# SensorPod.net
KiCad netlist of a schematic drawn in EAGLE
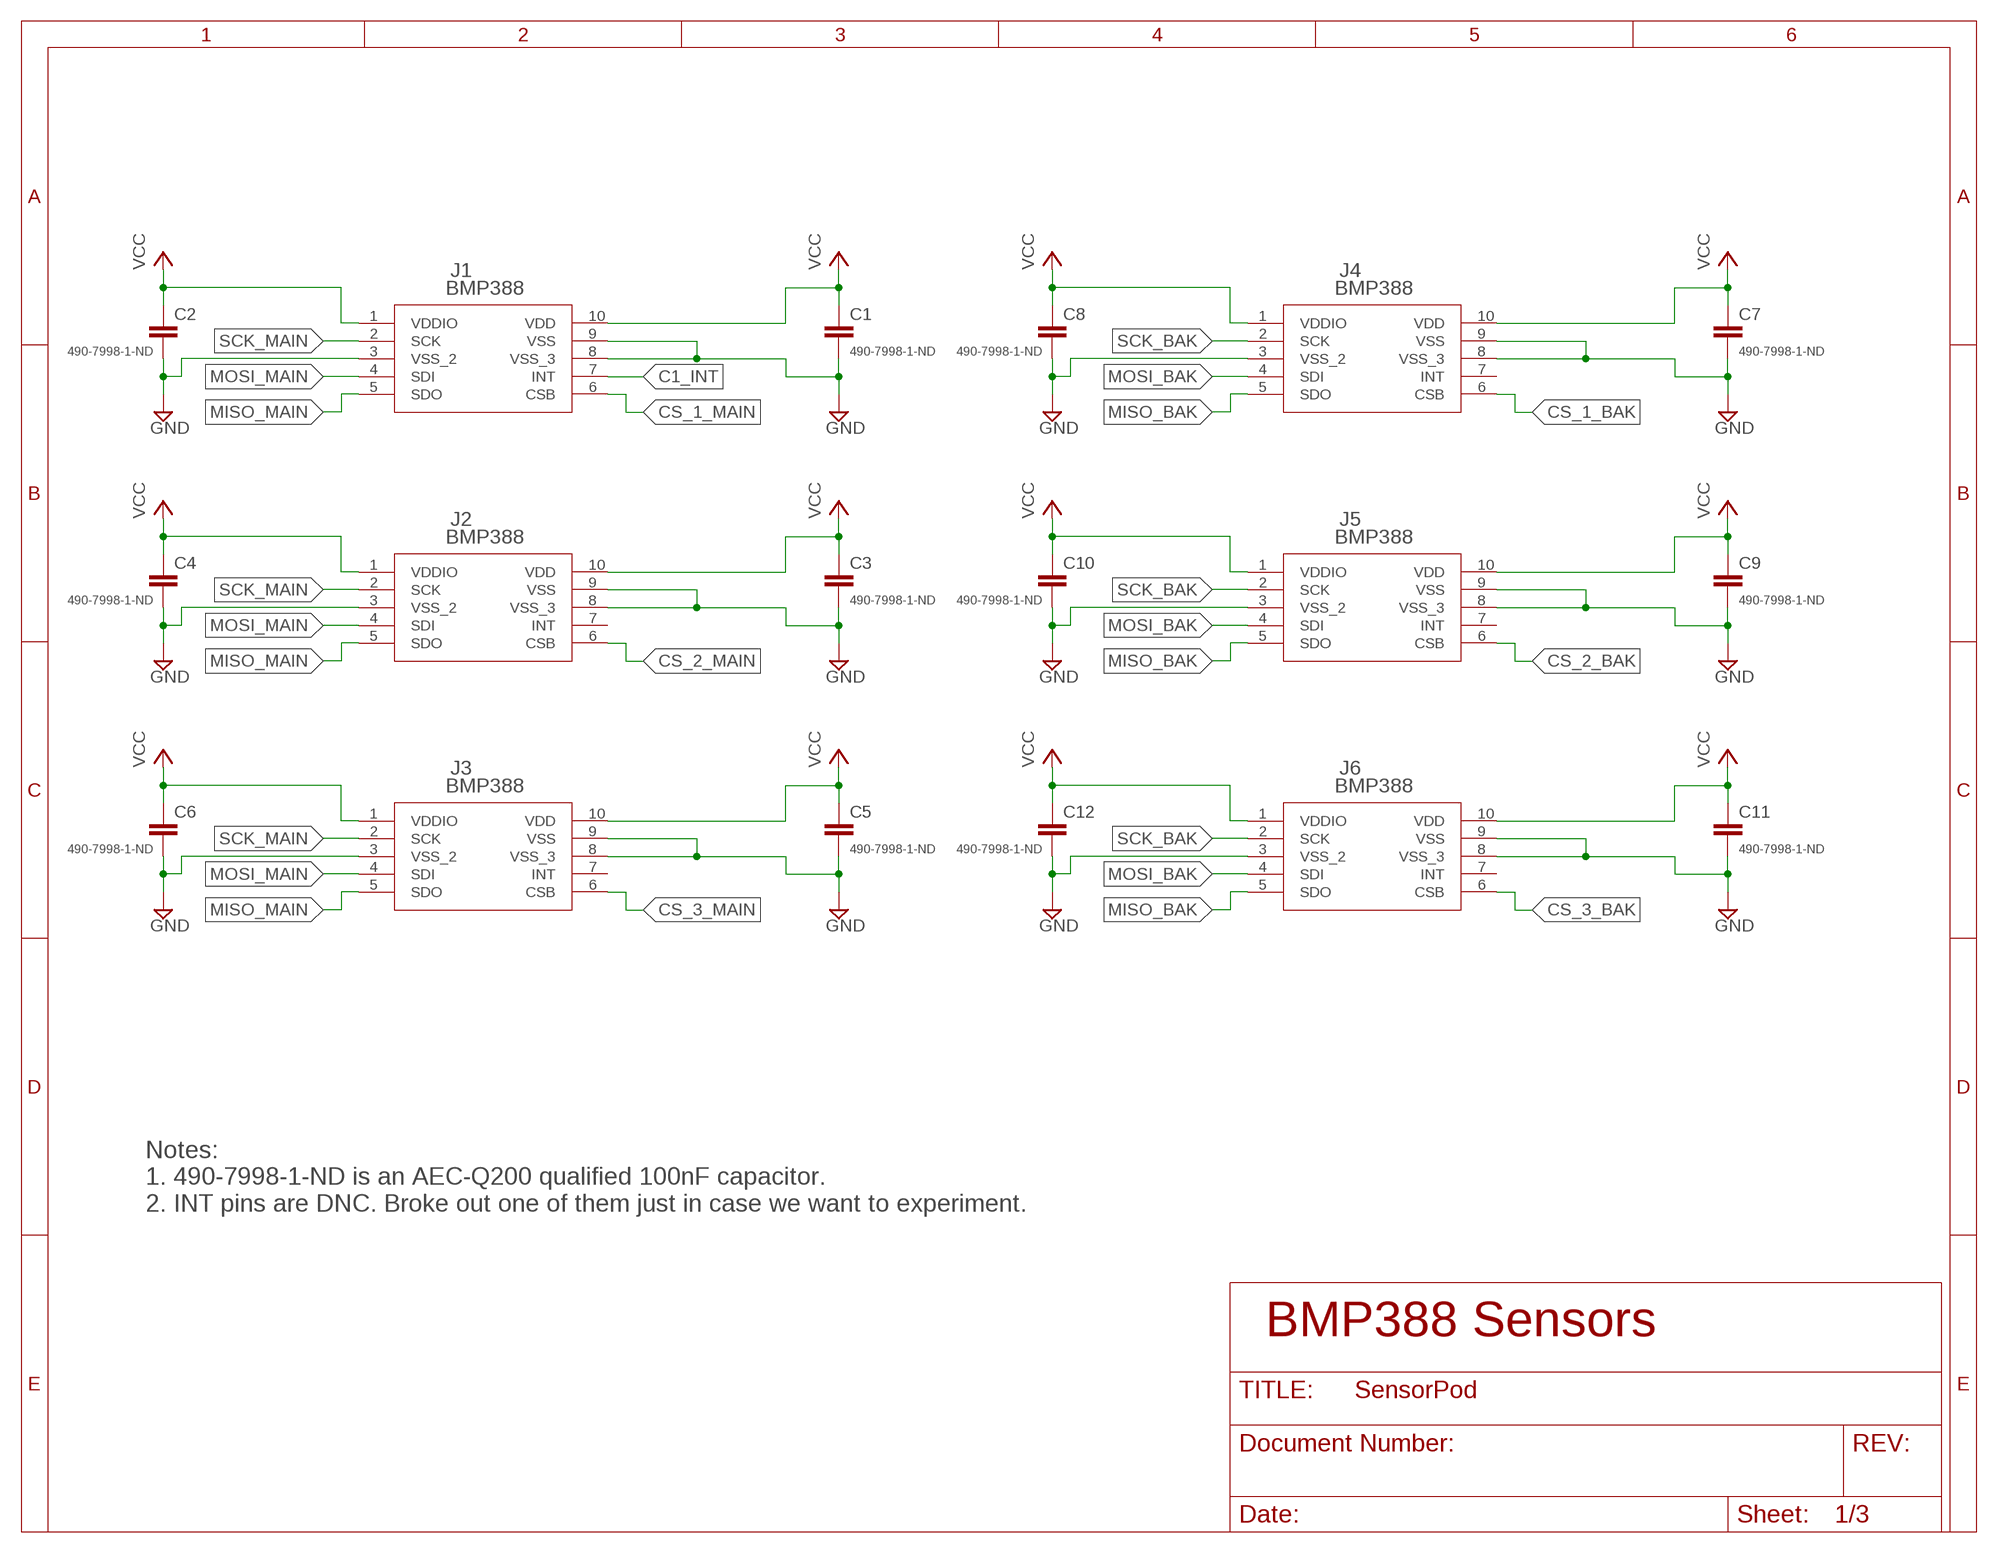
[diagram p0: schematic, sheet 1]
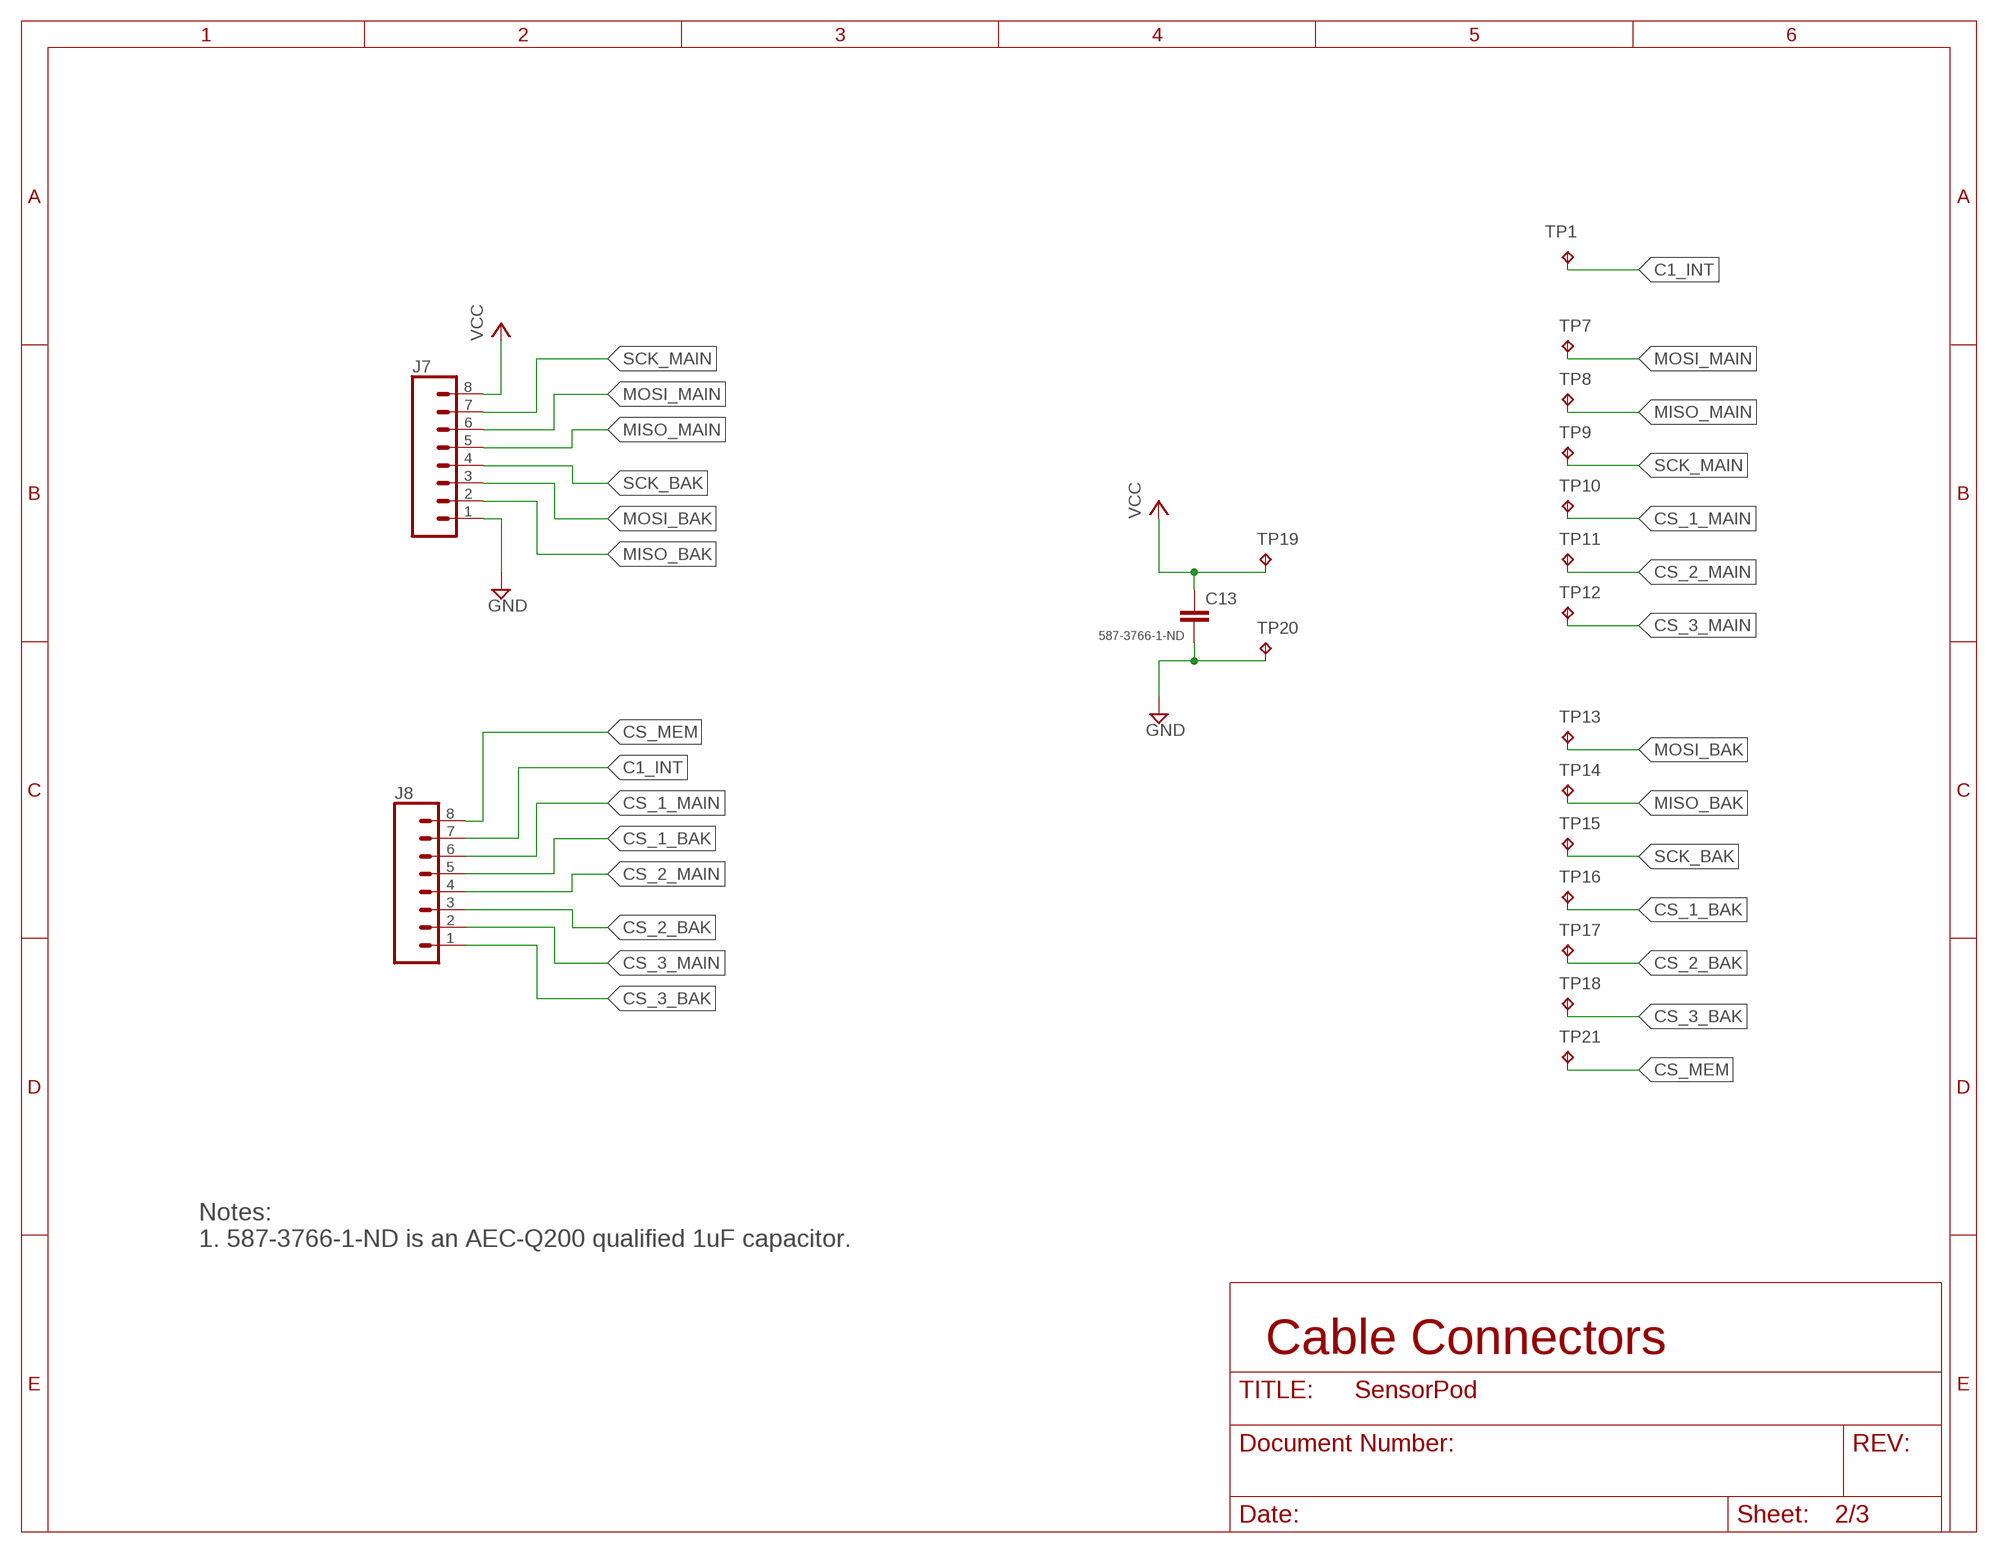
[diagram p1: schematic, sheet 2]
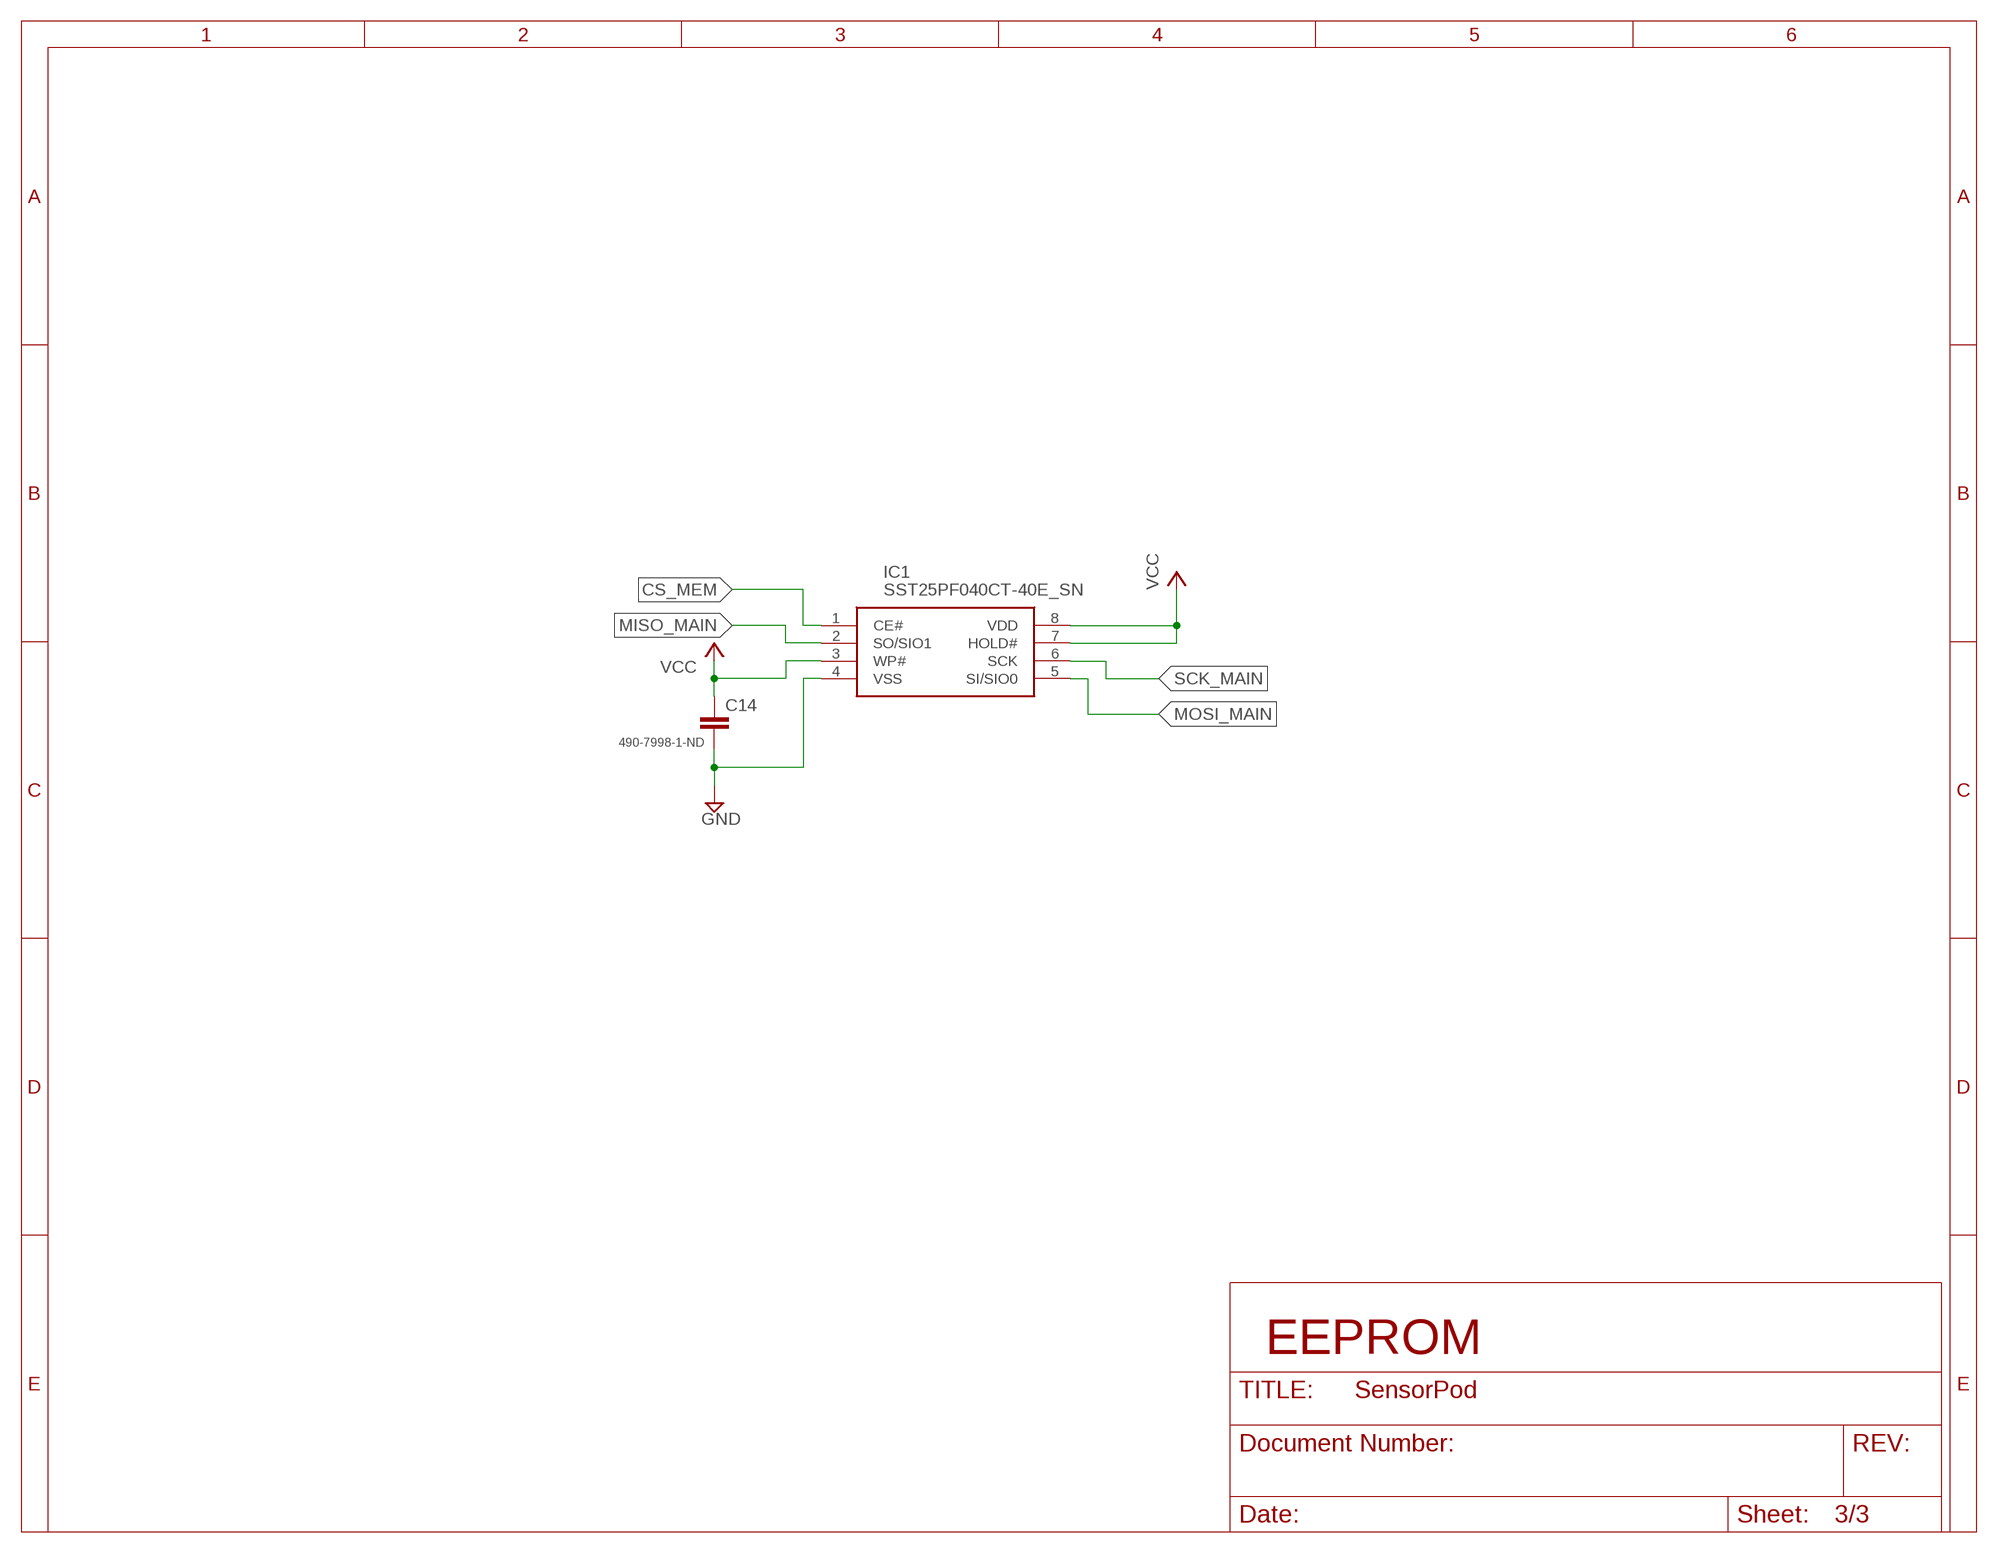
[diagram p2: schematic, sheet 3]

(export (version "E")
  (design (tool "Eeschema 10.0.6"))
  (components
    (comp (ref "C1")
      (value "490-7998-1-ND")
      (footprint "eagle-import:C0402")
      (libsource (lib "eagle-import") (part "C-EUC0402"))
    )
    (comp (ref "C2")
      (value "490-7998-1-ND")
      (footprint "eagle-import:C0402")
      (libsource (lib "eagle-import") (part "C-EUC0402"))
    )
    (comp (ref "C3")
      (value "490-7998-1-ND")
      (footprint "eagle-import:C0402")
      (libsource (lib "eagle-import") (part "C-EUC0402"))
    )
    (comp (ref "C4")
      (value "490-7998-1-ND")
      (footprint "eagle-import:C0402")
      (libsource (lib "eagle-import") (part "C-EUC0402"))
    )
    (comp (ref "C5")
      (value "490-7998-1-ND")
      (footprint "eagle-import:C0402")
      (libsource (lib "eagle-import") (part "C-EUC0402"))
    )
    (comp (ref "C6")
      (value "490-7998-1-ND")
      (footprint "eagle-import:C0402")
      (libsource (lib "eagle-import") (part "C-EUC0402"))
    )
    (comp (ref "C7")
      (value "490-7998-1-ND")
      (footprint "eagle-import:C0402")
      (libsource (lib "eagle-import") (part "C-EUC0402"))
    )
    (comp (ref "C8")
      (value "490-7998-1-ND")
      (footprint "eagle-import:C0402")
      (libsource (lib "eagle-import") (part "C-EUC0402"))
    )
    (comp (ref "C9")
      (value "490-7998-1-ND")
      (footprint "eagle-import:C0402")
      (libsource (lib "eagle-import") (part "C-EUC0402"))
    )
    (comp (ref "C10")
      (value "490-7998-1-ND")
      (footprint "eagle-import:C0402")
      (libsource (lib "eagle-import") (part "C-EUC0402"))
    )
    (comp (ref "C11")
      (value "490-7998-1-ND")
      (footprint "eagle-import:C0402")
      (libsource (lib "eagle-import") (part "C-EUC0402"))
    )
    (comp (ref "C12")
      (value "490-7998-1-ND")
      (footprint "eagle-import:C0402")
      (libsource (lib "eagle-import") (part "C-EUC0402"))
    )
    (comp (ref "J1")
      (value "BMP388")
      (footprint "eagle-import:QFN_BMP388")
      (fields (field (name "COPYRIGHT") "Copyright (C) 2018 Accelerated Designs. All rights reserved"))
      (libsource (lib "eagle-import") (part "BMP388"))
    )
    (comp (ref "J2")
      (value "BMP388")
      (footprint "eagle-import:QFN_BMP388")
      (fields (field (name "COPYRIGHT") "Copyright (C) 2018 Accelerated Designs. All rights reserved"))
      (libsource (lib "eagle-import") (part "BMP388"))
    )
    (comp (ref "J3")
      (value "BMP388")
      (footprint "eagle-import:QFN_BMP388")
      (fields (field (name "COPYRIGHT") "Copyright (C) 2018 Accelerated Designs. All rights reserved"))
      (libsource (lib "eagle-import") (part "BMP388"))
    )
    (comp (ref "J4")
      (value "BMP388")
      (footprint "eagle-import:QFN_BMP388")
      (fields (field (name "COPYRIGHT") "Copyright (C) 2018 Accelerated Designs. All rights reserved"))
      (libsource (lib "eagle-import") (part "BMP388"))
    )
    (comp (ref "J5")
      (value "BMP388")
      (footprint "eagle-import:QFN_BMP388")
      (fields (field (name "COPYRIGHT") "Copyright (C) 2018 Accelerated Designs. All rights reserved"))
      (libsource (lib "eagle-import") (part "BMP388"))
    )
    (comp (ref "J6")
      (value "BMP388")
      (footprint "eagle-import:QFN_BMP388")
      (fields (field (name "COPYRIGHT") "Copyright (C) 2018 Accelerated Designs. All rights reserved"))
      (libsource (lib "eagle-import") (part "BMP388"))
    )
    (comp (ref "C14")
      (value "490-7998-1-ND")
      (footprint "eagle-import:C0402")
      (libsource (lib "eagle-import") (part "C-EUC0402"))
    )
    (comp (ref "IC1")
      (value "SST25PF040CT-40E_SN")
      (footprint "eagle-import:SOIC127P600X175-8N")
      (fields
        (field (name "MANUFACTURER_PART_NUMBER") "SST25PF040CT-40E/SN")
        (field (name "MOUSER_PART_NUMBER") "579-T25PF040CT-40ESN")
      )
      (libsource (lib "eagle-import") (part "SST25PF040CT-40E_SN"))
    )
    (comp (ref "C13")
      (value "587-3766-1-ND")
      (footprint "eagle-import:C0402")
      (libsource (lib "eagle-import") (part "C-EUC0402"))
    )
    (comp (ref "J7")
      (value "CONN_08\"")
      (footprint "eagle-import:1X08")
      (libsource (lib "eagle-import") (part "CONN_08{dblquote}"))
    )
    (comp (ref "J8")
      (value "CONN_08\"")
      (footprint "eagle-import:1X08")
      (libsource (lib "eagle-import") (part "CONN_08{dblquote}"))
    )
    (comp (ref "TP1")
      (value "TPB1,27")
      (footprint "eagle-import:B1,27")
      (libsource (lib "eagle-import") (part "TPB1,27"))
    )
    (comp (ref "TP7")
      (value "TPB1,27")
      (footprint "eagle-import:B1,27")
      (libsource (lib "eagle-import") (part "TPB1,27"))
    )
    (comp (ref "TP8")
      (value "TPB1,27")
      (footprint "eagle-import:B1,27")
      (libsource (lib "eagle-import") (part "TPB1,27"))
    )
    (comp (ref "TP9")
      (value "TPB1,27")
      (footprint "eagle-import:B1,27")
      (libsource (lib "eagle-import") (part "TPB1,27"))
    )
    (comp (ref "TP10")
      (value "TPB1,27")
      (footprint "eagle-import:B1,27")
      (libsource (lib "eagle-import") (part "TPB1,27"))
    )
    (comp (ref "TP11")
      (value "TPB1,27")
      (footprint "eagle-import:B1,27")
      (libsource (lib "eagle-import") (part "TPB1,27"))
    )
    (comp (ref "TP12")
      (value "TPB1,27")
      (footprint "eagle-import:B1,27")
      (libsource (lib "eagle-import") (part "TPB1,27"))
    )
    (comp (ref "TP13")
      (value "TPB1,27")
      (footprint "eagle-import:B1,27")
      (libsource (lib "eagle-import") (part "TPB1,27"))
    )
    (comp (ref "TP14")
      (value "TPB1,27")
      (footprint "eagle-import:B1,27")
      (libsource (lib "eagle-import") (part "TPB1,27"))
    )
    (comp (ref "TP15")
      (value "TPB1,27")
      (footprint "eagle-import:B1,27")
      (libsource (lib "eagle-import") (part "TPB1,27"))
    )
    (comp (ref "TP16")
      (value "TPB1,27")
      (footprint "eagle-import:B1,27")
      (libsource (lib "eagle-import") (part "TPB1,27"))
    )
    (comp (ref "TP17")
      (value "TPB1,27")
      (footprint "eagle-import:B1,27")
      (libsource (lib "eagle-import") (part "TPB1,27"))
    )
    (comp (ref "TP18")
      (value "TPB1,27")
      (footprint "eagle-import:B1,27")
      (libsource (lib "eagle-import") (part "TPB1,27"))
    )
    (comp (ref "TP19")
      (value "TPB1,27")
      (footprint "eagle-import:B1,27")
      (libsource (lib "eagle-import") (part "TPB1,27"))
    )
    (comp (ref "TP20")
      (value "TPB1,27")
      (footprint "eagle-import:B1,27")
      (libsource (lib "eagle-import") (part "TPB1,27"))
    )
    (comp (ref "TP21")
      (value "TPB1,27")
      (footprint "eagle-import:B1,27")
      (libsource (lib "eagle-import") (part "TPB1,27"))
    )
  )
  (nets
    (net (code "1") (name "C1_INT") (class "Default")
      (node (ref "J1") (pin "7") (pinfunction "INT_7") (pintype "passive"))
      (node (ref "J8") (pin "7") (pinfunction "7_7") (pintype "passive"))
      (node (ref "TP1") (pin "TP") (pinfunction "TP_TP") (pintype "input"))
    )
    (net (code "2") (name "CS_1_BAK") (class "Default")
      (node (ref "J4") (pin "6") (pinfunction "CSB_6") (pintype "passive"))
      (node (ref "J8") (pin "5") (pinfunction "5_5") (pintype "passive"))
      (node (ref "TP16") (pin "TP") (pinfunction "TP_TP") (pintype "input"))
    )
    (net (code "3") (name "CS_1_MAIN") (class "Default")
      (node (ref "J1") (pin "6") (pinfunction "CSB_6") (pintype "passive"))
      (node (ref "J8") (pin "6") (pinfunction "6_6") (pintype "passive"))
      (node (ref "TP10") (pin "TP") (pinfunction "TP_TP") (pintype "input"))
    )
    (net (code "4") (name "CS_2_BAK") (class "Default")
      (node (ref "J5") (pin "6") (pinfunction "CSB_6") (pintype "passive"))
      (node (ref "J8") (pin "3") (pinfunction "3_3") (pintype "passive"))
      (node (ref "TP17") (pin "TP") (pinfunction "TP_TP") (pintype "input"))
    )
    (net (code "5") (name "CS_2_MAIN") (class "Default")
      (node (ref "J2") (pin "6") (pinfunction "CSB_6") (pintype "passive"))
      (node (ref "J8") (pin "4") (pinfunction "4_4") (pintype "passive"))
      (node (ref "TP11") (pin "TP") (pinfunction "TP_TP") (pintype "input"))
    )
    (net (code "6") (name "CS_3_BAK") (class "Default")
      (node (ref "J6") (pin "6") (pinfunction "CSB_6") (pintype "passive"))
      (node (ref "J8") (pin "1") (pinfunction "1_1") (pintype "passive"))
      (node (ref "TP18") (pin "TP") (pinfunction "TP_TP") (pintype "input"))
    )
    (net (code "7") (name "CS_3_MAIN") (class "Default")
      (node (ref "J3") (pin "6") (pinfunction "CSB_6") (pintype "passive"))
      (node (ref "J8") (pin "2") (pinfunction "2_2") (pintype "passive"))
      (node (ref "TP12") (pin "TP") (pinfunction "TP_TP") (pintype "input"))
    )
    (net (code "8") (name "CS_MEM") (class "Default")
      (node (ref "IC1") (pin "1") (pinfunction "CE#_1") (pintype "bidirectional"))
      (node (ref "J8") (pin "8") (pinfunction "8_8") (pintype "passive"))
      (node (ref "TP21") (pin "TP") (pinfunction "TP_TP") (pintype "input"))
    )
    (net (code "9") (name "GND") (class "Default")
      (node (ref "C1") (pin "2") (pinfunction "2_2") (pintype "passive"))
      (node (ref "C10") (pin "2") (pinfunction "2_2") (pintype "passive"))
      (node (ref "C11") (pin "2") (pinfunction "2_2") (pintype "passive"))
      (node (ref "C12") (pin "2") (pinfunction "2_2") (pintype "passive"))
      (node (ref "C13") (pin "2") (pinfunction "2_2") (pintype "passive"))
      (node (ref "C14") (pin "2") (pinfunction "2_2") (pintype "passive"))
      (node (ref "C2") (pin "2") (pinfunction "2_2") (pintype "passive"))
      (node (ref "C3") (pin "2") (pinfunction "2_2") (pintype "passive"))
      (node (ref "C4") (pin "2") (pinfunction "2_2") (pintype "passive"))
      (node (ref "C5") (pin "2") (pinfunction "2_2") (pintype "passive"))
      (node (ref "C6") (pin "2") (pinfunction "2_2") (pintype "passive"))
      (node (ref "C7") (pin "2") (pinfunction "2_2") (pintype "passive"))
      (node (ref "C8") (pin "2") (pinfunction "2_2") (pintype "passive"))
      (node (ref "C9") (pin "2") (pinfunction "2_2") (pintype "passive"))
      (node (ref "IC1") (pin "4") (pinfunction "VSS_4") (pintype "bidirectional"))
      (node (ref "J1") (pin "3") (pinfunction "VSS_2_3") (pintype "passive"))
      (node (ref "J1") (pin "8") (pinfunction "VSS_3_8") (pintype "passive"))
      (node (ref "J1") (pin "9") (pinfunction "VSS_9") (pintype "passive"))
      (node (ref "J2") (pin "3") (pinfunction "VSS_2_3") (pintype "passive"))
      (node (ref "J2") (pin "8") (pinfunction "VSS_3_8") (pintype "passive"))
      (node (ref "J2") (pin "9") (pinfunction "VSS_9") (pintype "passive"))
      (node (ref "J3") (pin "3") (pinfunction "VSS_2_3") (pintype "passive"))
      (node (ref "J3") (pin "8") (pinfunction "VSS_3_8") (pintype "passive"))
      (node (ref "J3") (pin "9") (pinfunction "VSS_9") (pintype "passive"))
      (node (ref "J4") (pin "3") (pinfunction "VSS_2_3") (pintype "passive"))
      (node (ref "J4") (pin "8") (pinfunction "VSS_3_8") (pintype "passive"))
      (node (ref "J4") (pin "9") (pinfunction "VSS_9") (pintype "passive"))
      (node (ref "J5") (pin "3") (pinfunction "VSS_2_3") (pintype "passive"))
      (node (ref "J5") (pin "8") (pinfunction "VSS_3_8") (pintype "passive"))
      (node (ref "J5") (pin "9") (pinfunction "VSS_9") (pintype "passive"))
      (node (ref "J6") (pin "3") (pinfunction "VSS_2_3") (pintype "passive"))
      (node (ref "J6") (pin "8") (pinfunction "VSS_3_8") (pintype "passive"))
      (node (ref "J6") (pin "9") (pinfunction "VSS_9") (pintype "passive"))
      (node (ref "J7") (pin "1") (pinfunction "1_1") (pintype "passive"))
      (node (ref "TP20") (pin "TP") (pinfunction "TP_TP") (pintype "input"))
    )
    (net (code "10") (name "MISO_BAK") (class "Default")
      (node (ref "J4") (pin "5") (pinfunction "SDO_5") (pintype "passive"))
      (node (ref "J5") (pin "5") (pinfunction "SDO_5") (pintype "passive"))
      (node (ref "J6") (pin "5") (pinfunction "SDO_5") (pintype "passive"))
      (node (ref "J7") (pin "2") (pinfunction "2_2") (pintype "passive"))
      (node (ref "TP14") (pin "TP") (pinfunction "TP_TP") (pintype "input"))
    )
    (net (code "11") (name "MISO_MAIN") (class "Default")
      (node (ref "IC1") (pin "2") (pinfunction "SO/SIO1_2") (pintype "bidirectional"))
      (node (ref "J1") (pin "5") (pinfunction "SDO_5") (pintype "passive"))
      (node (ref "J2") (pin "5") (pinfunction "SDO_5") (pintype "passive"))
      (node (ref "J3") (pin "5") (pinfunction "SDO_5") (pintype "passive"))
      (node (ref "J7") (pin "5") (pinfunction "5_5") (pintype "passive"))
      (node (ref "TP8") (pin "TP") (pinfunction "TP_TP") (pintype "input"))
    )
    (net (code "12") (name "MOSI_BAK") (class "Default")
      (node (ref "J4") (pin "4") (pinfunction "SDI_4") (pintype "passive"))
      (node (ref "J5") (pin "4") (pinfunction "SDI_4") (pintype "passive"))
      (node (ref "J6") (pin "4") (pinfunction "SDI_4") (pintype "passive"))
      (node (ref "J7") (pin "3") (pinfunction "3_3") (pintype "passive"))
      (node (ref "TP13") (pin "TP") (pinfunction "TP_TP") (pintype "input"))
    )
    (net (code "13") (name "MOSI_MAIN") (class "Default")
      (node (ref "IC1") (pin "5") (pinfunction "SI/SIO0_5") (pintype "bidirectional"))
      (node (ref "J1") (pin "4") (pinfunction "SDI_4") (pintype "passive"))
      (node (ref "J2") (pin "4") (pinfunction "SDI_4") (pintype "passive"))
      (node (ref "J3") (pin "4") (pinfunction "SDI_4") (pintype "passive"))
      (node (ref "J7") (pin "6") (pinfunction "6_6") (pintype "passive"))
      (node (ref "TP7") (pin "TP") (pinfunction "TP_TP") (pintype "input"))
    )
    (net (code "14") (name "SCK_BAK") (class "Default")
      (node (ref "J4") (pin "2") (pinfunction "SCK_2") (pintype "passive"))
      (node (ref "J5") (pin "2") (pinfunction "SCK_2") (pintype "passive"))
      (node (ref "J6") (pin "2") (pinfunction "SCK_2") (pintype "passive"))
      (node (ref "J7") (pin "4") (pinfunction "4_4") (pintype "passive"))
      (node (ref "TP15") (pin "TP") (pinfunction "TP_TP") (pintype "input"))
    )
    (net (code "15") (name "SCK_MAIN") (class "Default")
      (node (ref "IC1") (pin "6") (pinfunction "SCK_6") (pintype "bidirectional"))
      (node (ref "J1") (pin "2") (pinfunction "SCK_2") (pintype "passive"))
      (node (ref "J2") (pin "2") (pinfunction "SCK_2") (pintype "passive"))
      (node (ref "J3") (pin "2") (pinfunction "SCK_2") (pintype "passive"))
      (node (ref "J7") (pin "7") (pinfunction "7_7") (pintype "passive"))
      (node (ref "TP9") (pin "TP") (pinfunction "TP_TP") (pintype "input"))
    )
    (net (code "16") (name "VCC") (class "Default")
      (node (ref "C1") (pin "1") (pinfunction "1_1") (pintype "passive"))
      (node (ref "C10") (pin "1") (pinfunction "1_1") (pintype "passive"))
      (node (ref "C11") (pin "1") (pinfunction "1_1") (pintype "passive"))
      (node (ref "C12") (pin "1") (pinfunction "1_1") (pintype "passive"))
      (node (ref "C13") (pin "1") (pinfunction "1_1") (pintype "passive"))
      (node (ref "C14") (pin "1") (pinfunction "1_1") (pintype "passive"))
      (node (ref "C2") (pin "1") (pinfunction "1_1") (pintype "passive"))
      (node (ref "C3") (pin "1") (pinfunction "1_1") (pintype "passive"))
      (node (ref "C4") (pin "1") (pinfunction "1_1") (pintype "passive"))
      (node (ref "C5") (pin "1") (pinfunction "1_1") (pintype "passive"))
      (node (ref "C6") (pin "1") (pinfunction "1_1") (pintype "passive"))
      (node (ref "C7") (pin "1") (pinfunction "1_1") (pintype "passive"))
      (node (ref "C8") (pin "1") (pinfunction "1_1") (pintype "passive"))
      (node (ref "C9") (pin "1") (pinfunction "1_1") (pintype "passive"))
      (node (ref "IC1") (pin "3") (pinfunction "WP#_3") (pintype "bidirectional"))
      (node (ref "IC1") (pin "7") (pinfunction "HOLD#_7") (pintype "bidirectional"))
      (node (ref "IC1") (pin "8") (pinfunction "VDD_8") (pintype "bidirectional"))
      (node (ref "J1") (pin "1") (pinfunction "VDDIO_1") (pintype "power_in"))
      (node (ref "J1") (pin "10") (pinfunction "VDD_10") (pintype "power_in"))
      (node (ref "J2") (pin "1") (pinfunction "VDDIO_1") (pintype "power_in"))
      (node (ref "J2") (pin "10") (pinfunction "VDD_10") (pintype "power_in"))
      (node (ref "J3") (pin "1") (pinfunction "VDDIO_1") (pintype "power_in"))
      (node (ref "J3") (pin "10") (pinfunction "VDD_10") (pintype "power_in"))
      (node (ref "J4") (pin "1") (pinfunction "VDDIO_1") (pintype "power_in"))
      (node (ref "J4") (pin "10") (pinfunction "VDD_10") (pintype "power_in"))
      (node (ref "J5") (pin "1") (pinfunction "VDDIO_1") (pintype "power_in"))
      (node (ref "J5") (pin "10") (pinfunction "VDD_10") (pintype "power_in"))
      (node (ref "J6") (pin "1") (pinfunction "VDDIO_1") (pintype "power_in"))
      (node (ref "J6") (pin "10") (pinfunction "VDD_10") (pintype "power_in"))
      (node (ref "J7") (pin "8") (pinfunction "8_8") (pintype "passive"))
      (node (ref "TP19") (pin "TP") (pinfunction "TP_TP") (pintype "input"))
    )
    (net (code "17") (name "unconnected-(J2-INT-Pad7)") (class "Default")
      (node (ref "J2") (pin "7") (pinfunction "INT_7") (pintype "passive"))
    )
    (net (code "18") (name "unconnected-(J3-INT-Pad7)") (class "Default")
      (node (ref "J3") (pin "7") (pinfunction "INT_7") (pintype "passive"))
    )
    (net (code "19") (name "unconnected-(J4-INT-Pad7)") (class "Default")
      (node (ref "J4") (pin "7") (pinfunction "INT_7") (pintype "passive"))
    )
    (net (code "20") (name "unconnected-(J5-INT-Pad7)") (class "Default")
      (node (ref "J5") (pin "7") (pinfunction "INT_7") (pintype "passive"))
    )
    (net (code "21") (name "unconnected-(J6-INT-Pad7)") (class "Default")
      (node (ref "J6") (pin "7") (pinfunction "INT_7") (pintype "passive"))
    )
  )
)
